# rapidshark-clip-detector-mk-1_2b.net
KiCad netlist of a schematic drawn in EAGLE
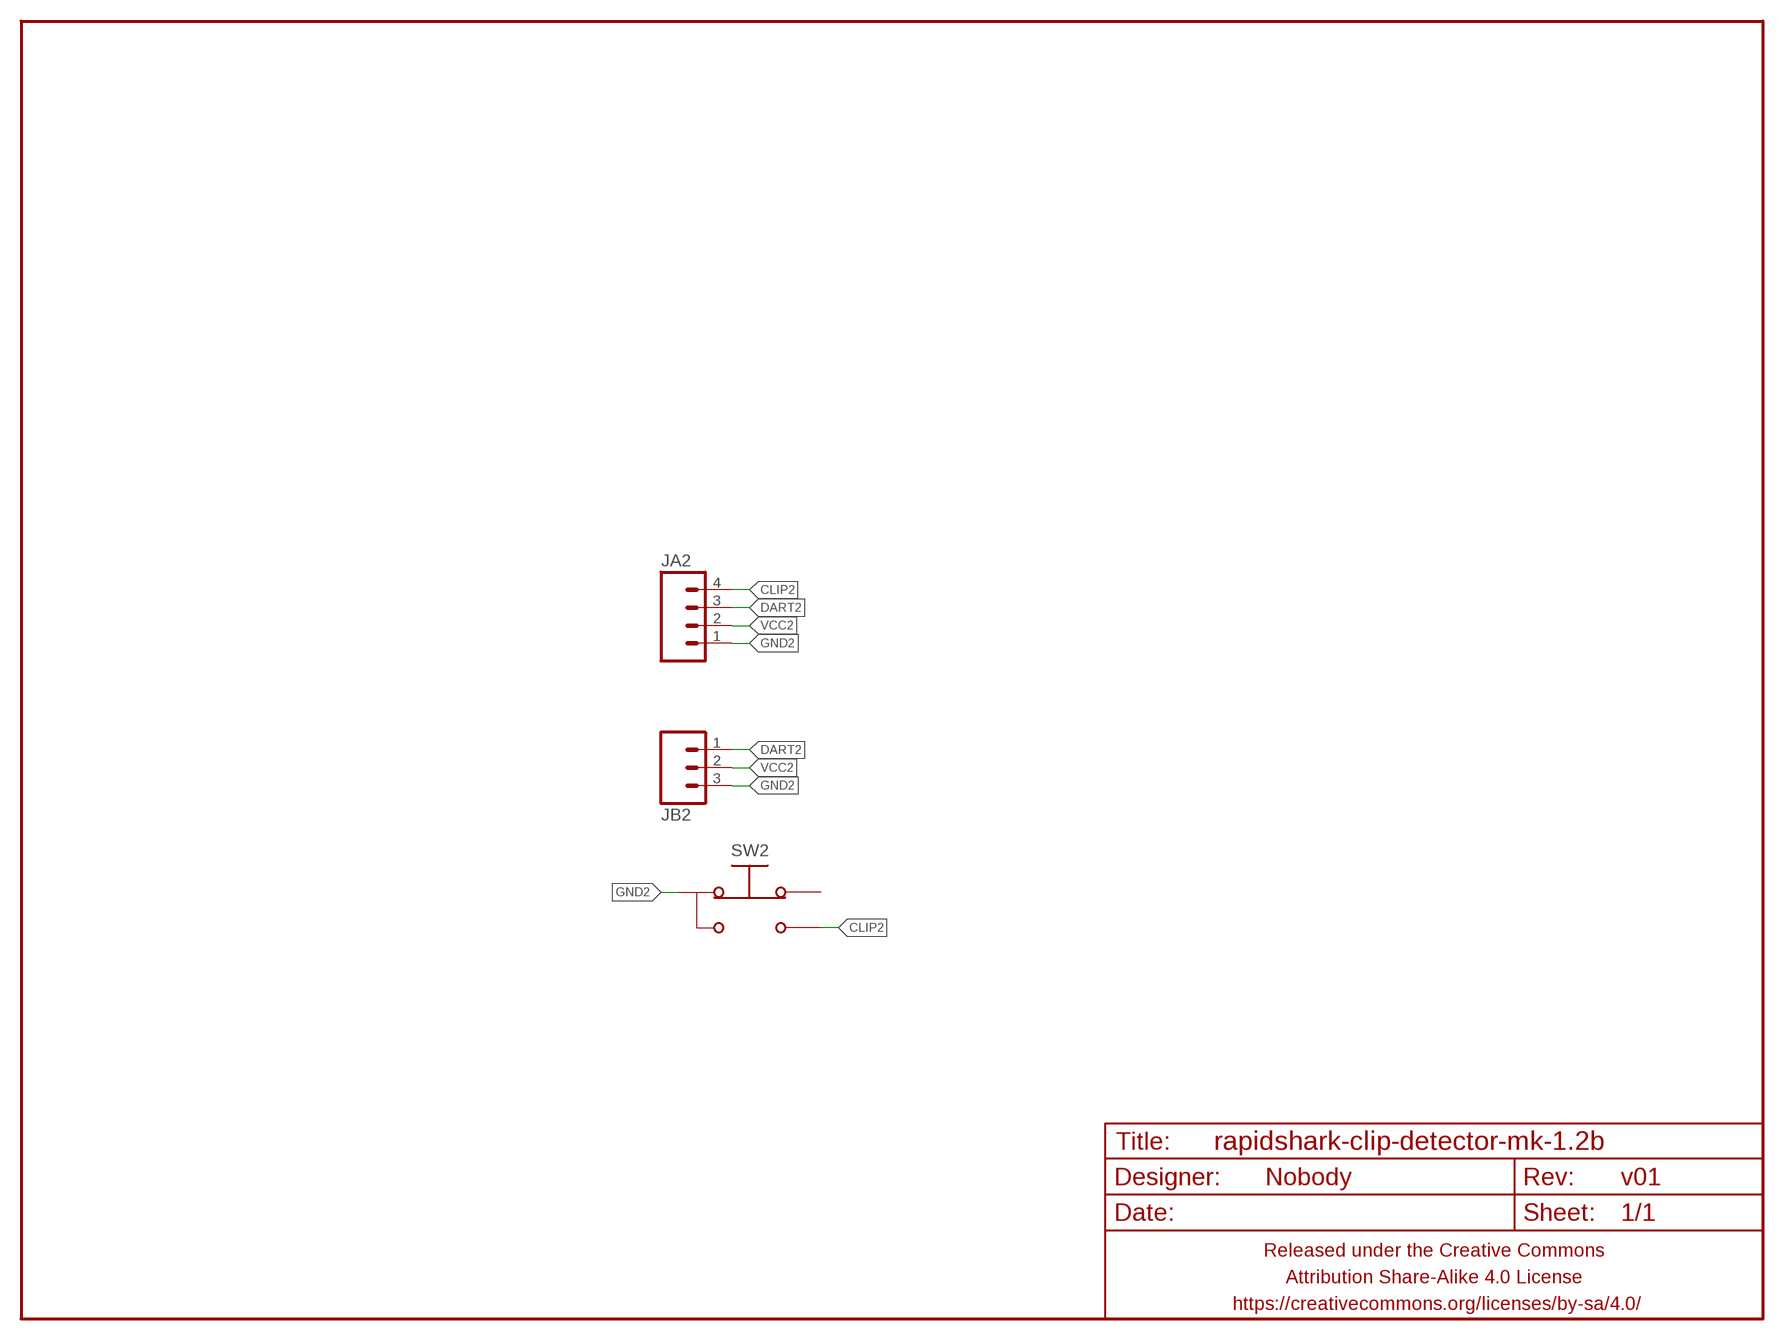
[diagram p0: schematic, sheet 1]

(export (version "E")
  (design (tool "Eeschema 10.0.6"))
  (components
    (comp (ref "FRAME1")
      (value "FRAME-LETTERNO_PACKAGE")
      (footprint "eagle-import:DUMMY")
      (fields (field (name "DESIGNER") "Nobody"))
      (libsource (lib "eagle-import") (part "FRAME-LETTERNO_PACKAGE"))
    )
    (comp (ref "JA2")
      (value "M04JST-PTH-VERT")
      (footprint "eagle-import:JST-4-PH-VERT-PTH")
      (libsource (lib "eagle-import") (part "M04JST-PTH-VERT"))
    )
    (comp (ref "JB2")
      (value "M03JST-PTH-VERT")
      (footprint "eagle-import:JST-3-PH-VERT-PTH")
      (libsource (lib "eagle-import") (part "M03JST-PTH-VERT"))
    )
    (comp (ref "SW2")
      (value "SPDT-NO-TACTPTH-RA-DETECT-3MM")
      (footprint "eagle-import:SWITCH-DETECH-SPDT-3MM")
      (libsource (lib "eagle-import") (part "SPDT-NO-TACTPTH-RA-DETECT-3MM"))
    )
  )
  (nets
    (net (code "1") (name "CLIP2") (class "Default")
      (node (ref "JA2") (pin "4") (pinfunction "4_4") (pintype "passive"))
      (node (ref "SW2") (pin "3") (pinfunction "NO_3") (pintype "bidirectional"))
    )
    (net (code "2") (name "DART2") (class "Default")
      (node (ref "JA2") (pin "3") (pinfunction "3_3") (pintype "passive"))
      (node (ref "JB2") (pin "1") (pinfunction "1_1") (pintype "passive"))
    )
    (net (code "3") (name "GND2") (class "Default")
      (node (ref "JA2") (pin "1") (pinfunction "1_1") (pintype "passive"))
      (node (ref "JB2") (pin "3") (pinfunction "3_3") (pintype "passive"))
      (node (ref "SW2") (pin "2") (pinfunction "COM_2") (pintype "bidirectional"))
    )
    (net (code "4") (name "VCC2") (class "Default")
      (node (ref "JA2") (pin "2") (pinfunction "2_2") (pintype "passive"))
      (node (ref "JB2") (pin "2") (pinfunction "2_2") (pintype "passive"))
    )
    (net (code "5") (name "unconnected-(SW2-NC-Pad1)") (class "Default")
      (node (ref "SW2") (pin "1") (pinfunction "NC_1") (pintype "bidirectional"))
    )
  )
)
